# Flow-Sensor.net
KiCad netlist of a schematic drawn in Altium Designer
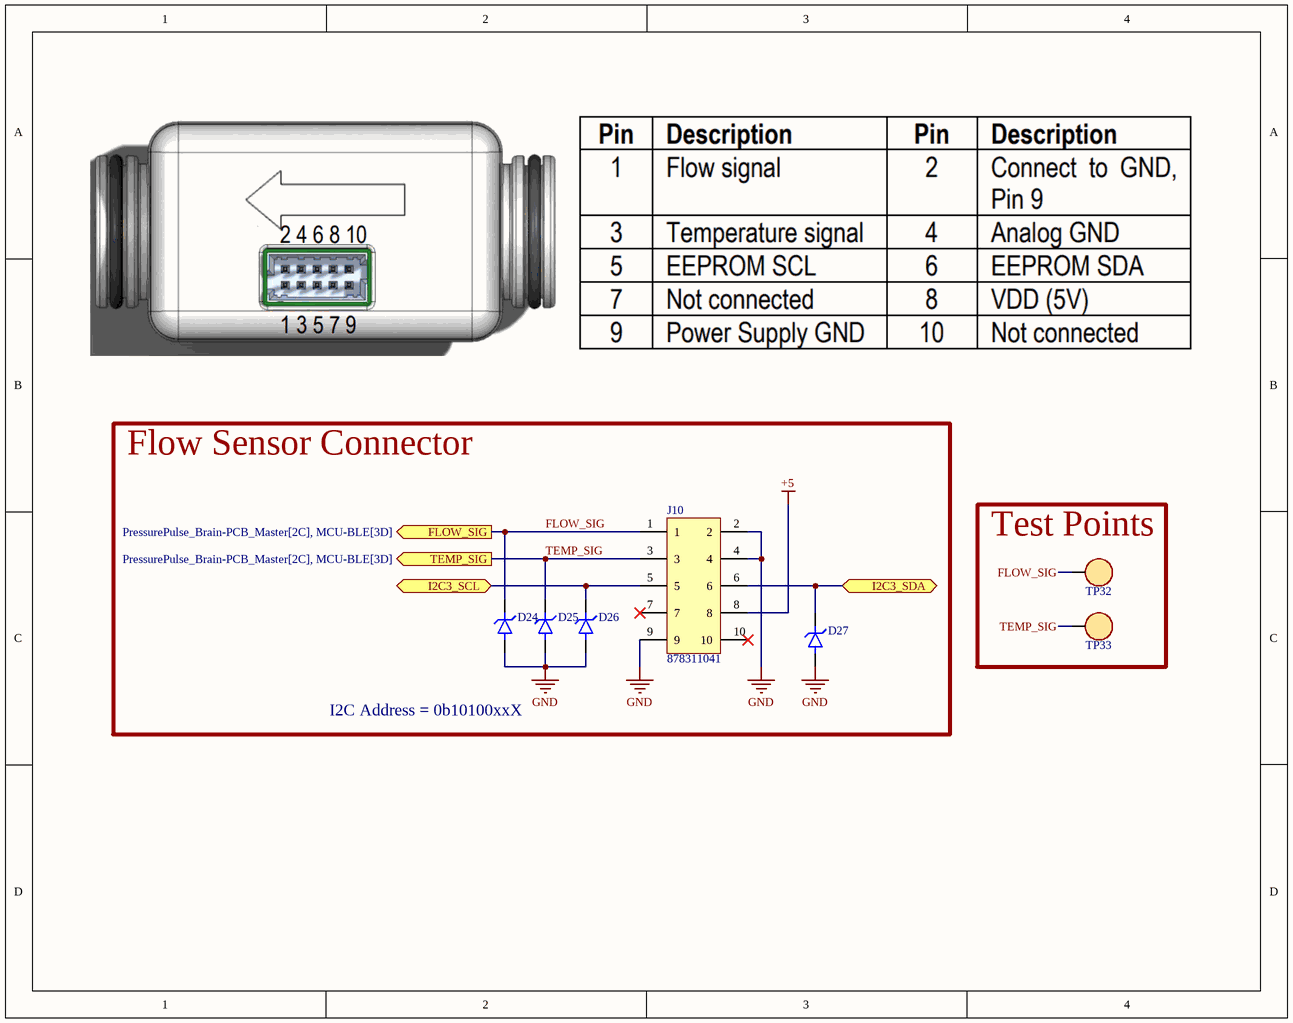
[diagram p0: Flow-Sensor.SchDoc]

(export (version "E")
  (design (tool "Eeschema 10.0.6"))
  (components
    (comp (ref "D24")
      (value "RCLAMP0521P.TCT")
      (footprint "PressurePulse:BDFN2C051V40")
      (description "25V Clamp 4A (8/20µs) Ipp Tvs Diode Surface Mount SLP1006P2")
      (fields (field (name "MFR") "BORN"))
      (libsource (lib "PressurePulse") (part "TVS DIODE"))
    )
    (comp (ref "D25")
      (value "RCLAMP0521P.TCT")
      (footprint "PressurePulse:BDFN2C051V40")
      (description "25V Clamp 4A (8/20µs) Ipp Tvs Diode Surface Mount SLP1006P2")
      (fields (field (name "MFR") "BORN"))
      (libsource (lib "PressurePulse") (part "TVS DIODE"))
    )
    (comp (ref "D26")
      (value "RCLAMP0521P.TCT")
      (footprint "PressurePulse:BDFN2C051V40")
      (description "25V Clamp 4A (8/20µs) Ipp Tvs Diode Surface Mount SLP1006P2")
      (fields (field (name "MFR") "BORN"))
      (libsource (lib "PressurePulse") (part "TVS DIODE"))
    )
    (comp (ref "D27")
      (value "RCLAMP0521P.TCT")
      (footprint "PressurePulse:BDFN2C051V40")
      (description "25V Clamp 4A (8/20µs) Ipp Tvs Diode Surface Mount SLP1006P2")
      (fields (field (name "MFR") "BORN"))
      (libsource (lib "PressurePulse") (part "TVS DIODE"))
    )
    (comp (ref "J10")
      (value "878311041")
      (footprint "PressurePulse:878311041")
      (fields (field (name "MFR") "Molex"))
      (libsource (lib "PressurePulse") (part "MOLEX 10 POS 2mm TH"))
    )
    (comp (ref "TP32")
      (value "RH-5019")
      (footprint "PressurePulse:TP - RH-5019")
      (fields (field (name "MFR") "ronghe"))
      (libsource (lib "PressurePulse") (part "TEST POINT"))
    )
    (comp (ref "TP33")
      (value "RH-5019")
      (footprint "PressurePulse:TP - RH-5019")
      (fields (field (name "MFR") "ronghe"))
      (libsource (lib "PressurePulse") (part "TEST POINT"))
    )
  )
  (nets
    (net (code "1") (name "+5") (class "Default")
      (node (ref "J10") (pin "8") (pinfunction "8_8") (pintype "passive"))
    )
    (net (code "2") (name "/FLOW_SIG") (class "Default")
      (node (ref "D24") (pin "K") (pinfunction "K_K") (pintype "passive"))
      (node (ref "J10") (pin "1") (pinfunction "1_1") (pintype "passive"))
      (node (ref "TP32") (pin "1") (pinfunction "1_1") (pintype "passive"))
    )
    (net (code "3") (name "/I2C3_SCL") (class "Default")
      (node (ref "D26") (pin "K") (pinfunction "K_K") (pintype "passive"))
      (node (ref "J10") (pin "5") (pinfunction "5_5") (pintype "passive"))
    )
    (net (code "4") (name "/I2C3_SDA") (class "Default")
      (node (ref "D27") (pin "K") (pinfunction "K_K") (pintype "passive"))
      (node (ref "J10") (pin "6") (pinfunction "6_6") (pintype "passive"))
    )
    (net (code "5") (name "/TEMP_SIG") (class "Default")
      (node (ref "D25") (pin "K") (pinfunction "K_K") (pintype "passive"))
      (node (ref "J10") (pin "3") (pinfunction "3_3") (pintype "passive"))
      (node (ref "TP33") (pin "1") (pinfunction "1_1") (pintype "passive"))
    )
    (net (code "6") (name "GND") (class "Default")
      (node (ref "D24") (pin "A") (pinfunction "A_A") (pintype "passive"))
      (node (ref "D25") (pin "A") (pinfunction "A_A") (pintype "passive"))
      (node (ref "D26") (pin "A") (pinfunction "A_A") (pintype "passive"))
      (node (ref "D27") (pin "A") (pinfunction "A_A") (pintype "passive"))
      (node (ref "J10") (pin "2") (pinfunction "2_2") (pintype "passive"))
      (node (ref "J10") (pin "4") (pinfunction "4_4") (pintype "passive"))
      (node (ref "J10") (pin "9") (pinfunction "9_9") (pintype "passive"))
    )
    (net (code "7") (name "unconnected-(J10-Pad7)") (class "Default")
      (node (ref "J10") (pin "7") (pinfunction "7_7") (pintype "passive+no_connect"))
    )
    (net (code "8") (name "unconnected-(J10-Pad10)") (class "Default")
      (node (ref "J10") (pin "10") (pinfunction "10_10") (pintype "passive+no_connect"))
    )
  )
)
